# STM32BluePill.net
KiCad netlist of a schematic drawn in EAGLE
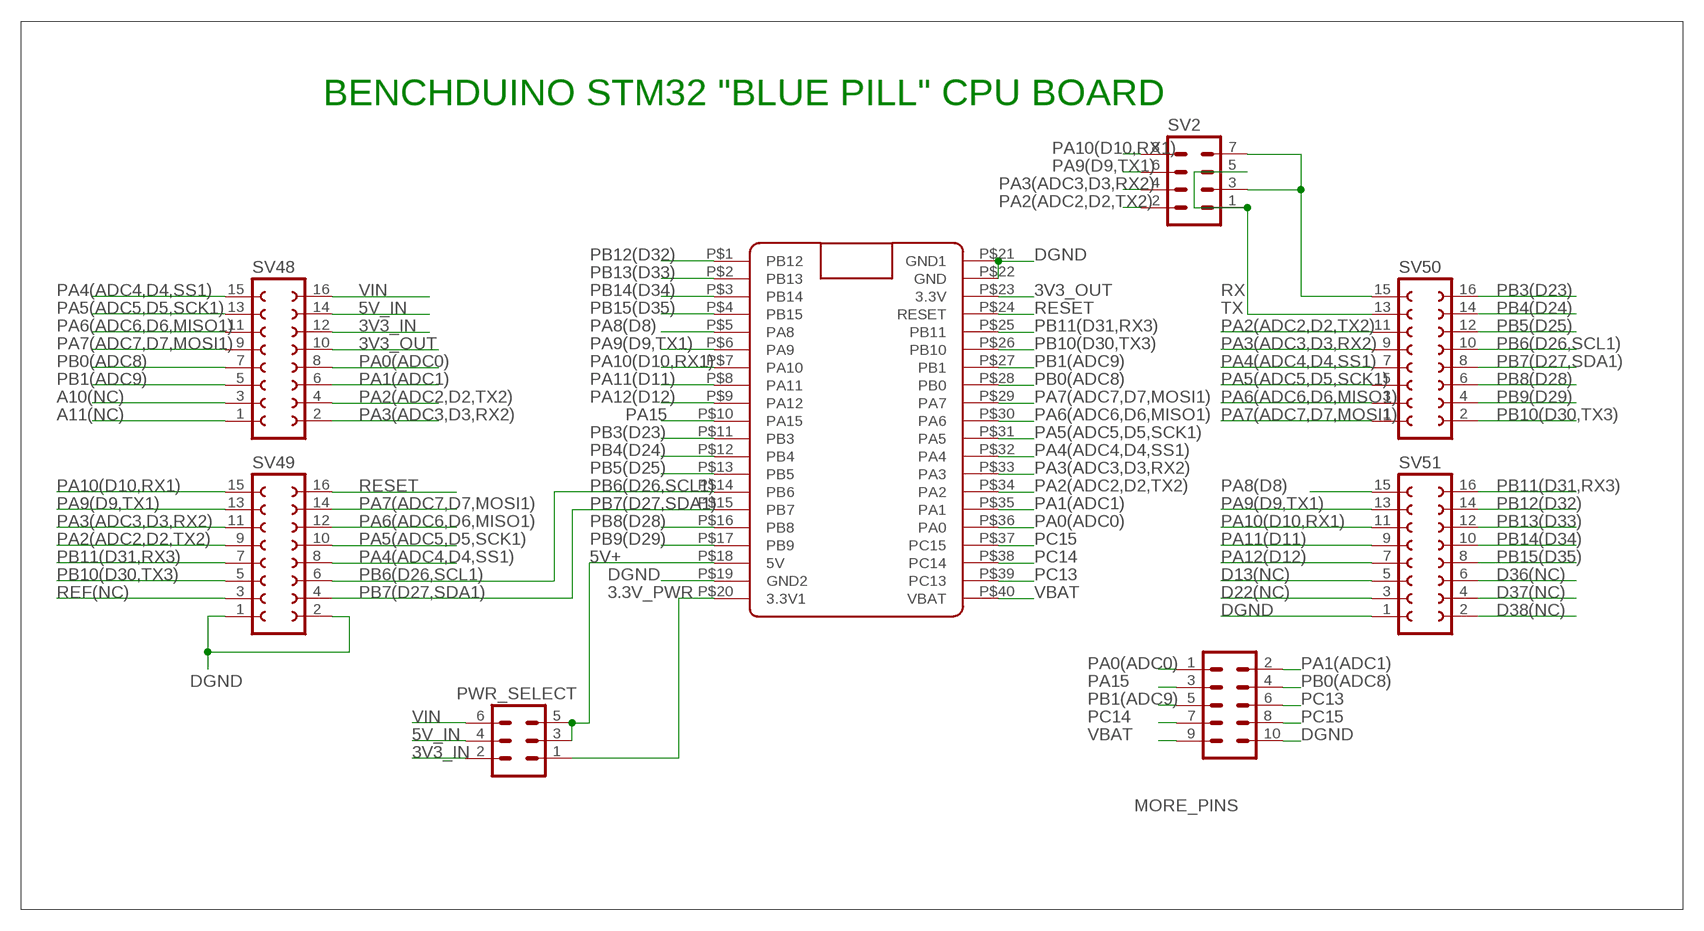
[diagram p0: schematic, sheet 1]

(export (version "E")
  (design (tool "Eeschema 10.0.6"))
  (components
    (comp (ref "MORE_PINS")
      (value "MA05-2")
      (footprint "eagle-import:MA05-2")
      (libsource (lib "eagle-import") (part "MA05-2"))
    )
    (comp (ref "PWR_SELECT")
      (value "MA03-2")
      (footprint "eagle-import:MA03-2")
      (libsource (lib "eagle-import") (part "MA03-2"))
    )
    (comp (ref "SV2")
      (value "MA04-2")
      (footprint "eagle-import:MA04-2")
      (libsource (lib "eagle-import") (part "MA04-2"))
    )
    (comp (ref "SV48")
      (value "FE08-2")
      (footprint "eagle-import:FE08-2")
      (libsource (lib "eagle-import") (part "FE08-2"))
    )
    (comp (ref "SV49")
      (value "FE08-2")
      (footprint "eagle-import:FE08-2")
      (libsource (lib "eagle-import") (part "FE08-2"))
    )
    (comp (ref "SV50")
      (value "FE08-2")
      (footprint "eagle-import:FE08-2")
      (libsource (lib "eagle-import") (part "FE08-2"))
    )
    (comp (ref "SV51")
      (value "FE08-2")
      (footprint "eagle-import:FE08-2")
      (libsource (lib "eagle-import") (part "FE08-2"))
    )
    (comp (ref "U$1")
      (value "BLUE_PILLADVANCED")
      (footprint "eagle-import:BLUE_PILL_ADV")
      (libsource (lib "eagle-import") (part "BLUE_PILLADVANCED"))
    )
  )
  (nets
    (net (code "1") (name "3.3V_PWR") (class "Default")
      (node (ref "PWR_SELECT") (pin "1") (pinfunction "1_1") (pintype "passive"))
      (node (ref "U$1") (pin "P$20") (pinfunction "3.3V1_P$20") (pintype "bidirectional"))
    )
    (net (code "2") (name "3V3_IN") (class "Default")
      (node (ref "PWR_SELECT") (pin "2") (pinfunction "2_2") (pintype "passive"))
      (node (ref "SV48") (pin "12") (pinfunction "12_12") (pintype "passive"))
    )
    (net (code "3") (name "3V3_OUT") (class "Default")
      (node (ref "SV48") (pin "10") (pinfunction "10_10") (pintype "passive"))
      (node (ref "U$1") (pin "P$23") (pinfunction "3.3V_P$23") (pintype "bidirectional"))
    )
    (net (code "4") (name "5V+") (class "Default")
      (node (ref "PWR_SELECT") (pin "3") (pinfunction "3_3") (pintype "passive"))
      (node (ref "PWR_SELECT") (pin "5") (pinfunction "5_5") (pintype "passive"))
      (node (ref "U$1") (pin "P$18") (pinfunction "5V_P$18") (pintype "bidirectional"))
    )
    (net (code "5") (name "5V_IN") (class "Default")
      (node (ref "PWR_SELECT") (pin "4") (pinfunction "4_4") (pintype "passive"))
      (node (ref "SV48") (pin "14") (pinfunction "14_14") (pintype "passive"))
    )
    (net (code "6") (name "A10(NC)") (class "Default")
      (node (ref "SV48") (pin "3") (pinfunction "3_3") (pintype "passive"))
    )
    (net (code "7") (name "A11(NC)") (class "Default")
      (node (ref "SV48") (pin "1") (pinfunction "1_1") (pintype "passive"))
    )
    (net (code "8") (name "D13(NC)") (class "Default")
      (node (ref "SV51") (pin "5") (pinfunction "5_5") (pintype "passive"))
    )
    (net (code "9") (name "D22(NC)") (class "Default")
      (node (ref "SV51") (pin "3") (pinfunction "3_3") (pintype "passive"))
    )
    (net (code "10") (name "D36(NC)") (class "Default")
      (node (ref "SV51") (pin "6") (pinfunction "6_6") (pintype "passive"))
    )
    (net (code "11") (name "D37(NC)") (class "Default")
      (node (ref "SV51") (pin "4") (pinfunction "4_4") (pintype "passive"))
    )
    (net (code "12") (name "D38(NC)") (class "Default")
      (node (ref "SV51") (pin "2") (pinfunction "2_2") (pintype "passive"))
    )
    (net (code "13") (name "DGND") (class "Default")
      (node (ref "MORE_PINS") (pin "10") (pinfunction "10_10") (pintype "passive"))
      (node (ref "SV49") (pin "1") (pinfunction "1_1") (pintype "passive"))
      (node (ref "SV49") (pin "2") (pinfunction "2_2") (pintype "passive"))
      (node (ref "SV51") (pin "1") (pinfunction "1_1") (pintype "passive"))
      (node (ref "U$1") (pin "P$19") (pinfunction "GND2_P$19") (pintype "bidirectional"))
      (node (ref "U$1") (pin "P$21") (pinfunction "GND1_P$21") (pintype "power_in"))
      (node (ref "U$1") (pin "P$22") (pinfunction "GND_P$22") (pintype "bidirectional"))
    )
    (net (code "14") (name "PA0(ADC0)") (class "Default")
      (node (ref "MORE_PINS") (pin "1") (pinfunction "1_1") (pintype "passive"))
      (node (ref "SV48") (pin "8") (pinfunction "8_8") (pintype "passive"))
      (node (ref "U$1") (pin "P$36") (pinfunction "PA0_P$36") (pintype "bidirectional"))
    )
    (net (code "15") (name "PA1(ADC1)") (class "Default")
      (node (ref "MORE_PINS") (pin "2") (pinfunction "2_2") (pintype "passive"))
      (node (ref "SV48") (pin "6") (pinfunction "6_6") (pintype "passive"))
      (node (ref "U$1") (pin "P$35") (pinfunction "PA1_P$35") (pintype "bidirectional"))
    )
    (net (code "16") (name "PA2(ADC2,D2,TX2)") (class "Default")
      (node (ref "SV2") (pin "2") (pinfunction "2_2") (pintype "passive"))
      (node (ref "SV48") (pin "4") (pinfunction "4_4") (pintype "passive"))
      (node (ref "SV49") (pin "9") (pinfunction "9_9") (pintype "passive"))
      (node (ref "SV50") (pin "11") (pinfunction "11_11") (pintype "passive"))
      (node (ref "U$1") (pin "P$34") (pinfunction "PA2_P$34") (pintype "bidirectional"))
    )
    (net (code "17") (name "PA3(ADC3,D3,RX2)") (class "Default")
      (node (ref "SV2") (pin "4") (pinfunction "4_4") (pintype "passive"))
      (node (ref "SV48") (pin "2") (pinfunction "2_2") (pintype "passive"))
      (node (ref "SV49") (pin "11") (pinfunction "11_11") (pintype "passive"))
      (node (ref "SV50") (pin "9") (pinfunction "9_9") (pintype "passive"))
      (node (ref "U$1") (pin "P$33") (pinfunction "PA3_P$33") (pintype "bidirectional"))
    )
    (net (code "18") (name "PA4(ADC4,D4,SS1)") (class "Default")
      (node (ref "SV48") (pin "15") (pinfunction "15_15") (pintype "passive"))
      (node (ref "SV49") (pin "8") (pinfunction "8_8") (pintype "passive"))
      (node (ref "SV50") (pin "7") (pinfunction "7_7") (pintype "passive"))
      (node (ref "U$1") (pin "P$32") (pinfunction "PA4_P$32") (pintype "bidirectional"))
    )
    (net (code "19") (name "PA5(ADC5,D5,SCK1)") (class "Default")
      (node (ref "SV48") (pin "13") (pinfunction "13_13") (pintype "passive"))
      (node (ref "SV49") (pin "10") (pinfunction "10_10") (pintype "passive"))
      (node (ref "SV50") (pin "5") (pinfunction "5_5") (pintype "passive"))
      (node (ref "U$1") (pin "P$31") (pinfunction "PA5_P$31") (pintype "bidirectional"))
    )
    (net (code "20") (name "PA6(ADC6,D6,MISO1)") (class "Default")
      (node (ref "SV48") (pin "11") (pinfunction "11_11") (pintype "passive"))
      (node (ref "SV49") (pin "12") (pinfunction "12_12") (pintype "passive"))
      (node (ref "SV50") (pin "3") (pinfunction "3_3") (pintype "passive"))
      (node (ref "U$1") (pin "P$30") (pinfunction "PA6_P$30") (pintype "bidirectional"))
    )
    (net (code "21") (name "PA7(ADC7,D7,MOSI1)") (class "Default")
      (node (ref "SV48") (pin "9") (pinfunction "9_9") (pintype "passive"))
      (node (ref "SV49") (pin "14") (pinfunction "14_14") (pintype "passive"))
      (node (ref "SV50") (pin "1") (pinfunction "1_1") (pintype "passive"))
      (node (ref "U$1") (pin "P$29") (pinfunction "PA7_P$29") (pintype "bidirectional"))
    )
    (net (code "22") (name "PA8(D8)") (class "Default")
      (node (ref "SV51") (pin "15") (pinfunction "15_15") (pintype "passive"))
      (node (ref "U$1") (pin "P$5") (pinfunction "PA8_P$5") (pintype "bidirectional"))
    )
    (net (code "23") (name "PA9(D9,TX1)") (class "Default")
      (node (ref "SV2") (pin "6") (pinfunction "6_6") (pintype "passive"))
      (node (ref "SV49") (pin "13") (pinfunction "13_13") (pintype "passive"))
      (node (ref "SV51") (pin "13") (pinfunction "13_13") (pintype "passive"))
      (node (ref "U$1") (pin "P$6") (pinfunction "PA9_P$6") (pintype "bidirectional"))
    )
    (net (code "24") (name "PA10(D10,RX1)") (class "Default")
      (node (ref "SV2") (pin "8") (pinfunction "8_8") (pintype "passive"))
      (node (ref "SV49") (pin "15") (pinfunction "15_15") (pintype "passive"))
      (node (ref "SV51") (pin "11") (pinfunction "11_11") (pintype "passive"))
      (node (ref "U$1") (pin "P$7") (pinfunction "PA10_P$7") (pintype "bidirectional"))
    )
    (net (code "25") (name "PA11(D11)") (class "Default")
      (node (ref "SV51") (pin "9") (pinfunction "9_9") (pintype "passive"))
      (node (ref "U$1") (pin "P$8") (pinfunction "PA11_P$8") (pintype "bidirectional"))
    )
    (net (code "26") (name "PA12(D12)") (class "Default")
      (node (ref "SV51") (pin "7") (pinfunction "7_7") (pintype "passive"))
      (node (ref "U$1") (pin "P$9") (pinfunction "PA12_P$9") (pintype "bidirectional"))
    )
    (net (code "27") (name "PA15") (class "Default")
      (node (ref "MORE_PINS") (pin "3") (pinfunction "3_3") (pintype "passive"))
      (node (ref "U$1") (pin "P$10") (pinfunction "PA15_P$10") (pintype "bidirectional"))
    )
    (net (code "28") (name "PB0(ADC8)") (class "Default")
      (node (ref "MORE_PINS") (pin "4") (pinfunction "4_4") (pintype "passive"))
      (node (ref "SV48") (pin "7") (pinfunction "7_7") (pintype "passive"))
      (node (ref "U$1") (pin "P$28") (pinfunction "PB0_P$28") (pintype "bidirectional"))
    )
    (net (code "29") (name "PB1(ADC9)") (class "Default")
      (node (ref "MORE_PINS") (pin "5") (pinfunction "5_5") (pintype "passive"))
      (node (ref "SV48") (pin "5") (pinfunction "5_5") (pintype "passive"))
      (node (ref "U$1") (pin "P$27") (pinfunction "PB1_P$27") (pintype "bidirectional"))
    )
    (net (code "30") (name "PB3(D23)") (class "Default")
      (node (ref "SV50") (pin "16") (pinfunction "16_16") (pintype "passive"))
      (node (ref "U$1") (pin "P$11") (pinfunction "PB3_P$11") (pintype "bidirectional"))
    )
    (net (code "31") (name "PB4(D24)") (class "Default")
      (node (ref "SV50") (pin "14") (pinfunction "14_14") (pintype "passive"))
      (node (ref "U$1") (pin "P$12") (pinfunction "PB4_P$12") (pintype "bidirectional"))
    )
    (net (code "32") (name "PB5(D25)") (class "Default")
      (node (ref "SV50") (pin "12") (pinfunction "12_12") (pintype "passive"))
      (node (ref "U$1") (pin "P$13") (pinfunction "PB5_P$13") (pintype "bidirectional"))
    )
    (net (code "33") (name "PB6(D26,SCL1)") (class "Default")
      (node (ref "SV49") (pin "6") (pinfunction "6_6") (pintype "passive"))
      (node (ref "SV50") (pin "10") (pinfunction "10_10") (pintype "passive"))
      (node (ref "U$1") (pin "P$14") (pinfunction "PB6_P$14") (pintype "bidirectional"))
    )
    (net (code "34") (name "PB7(D27,SDA1)") (class "Default")
      (node (ref "SV49") (pin "4") (pinfunction "4_4") (pintype "passive"))
      (node (ref "SV50") (pin "8") (pinfunction "8_8") (pintype "passive"))
      (node (ref "U$1") (pin "P$15") (pinfunction "PB7_P$15") (pintype "bidirectional"))
    )
    (net (code "35") (name "PB8(D28)") (class "Default")
      (node (ref "SV50") (pin "6") (pinfunction "6_6") (pintype "passive"))
      (node (ref "U$1") (pin "P$16") (pinfunction "PB8_P$16") (pintype "bidirectional"))
    )
    (net (code "36") (name "PB9(D29)") (class "Default")
      (node (ref "SV50") (pin "4") (pinfunction "4_4") (pintype "passive"))
      (node (ref "U$1") (pin "P$17") (pinfunction "PB9_P$17") (pintype "bidirectional"))
    )
    (net (code "37") (name "PB10(D30,TX3)") (class "Default")
      (node (ref "SV49") (pin "5") (pinfunction "5_5") (pintype "passive"))
      (node (ref "SV50") (pin "2") (pinfunction "2_2") (pintype "passive"))
      (node (ref "U$1") (pin "P$26") (pinfunction "PB10_P$26") (pintype "bidirectional"))
    )
    (net (code "38") (name "PB11(D31,RX3)") (class "Default")
      (node (ref "SV49") (pin "7") (pinfunction "7_7") (pintype "passive"))
      (node (ref "SV51") (pin "16") (pinfunction "16_16") (pintype "passive"))
      (node (ref "U$1") (pin "P$25") (pinfunction "PB11_P$25") (pintype "bidirectional"))
    )
    (net (code "39") (name "PB12(D32)") (class "Default")
      (node (ref "SV51") (pin "14") (pinfunction "14_14") (pintype "passive"))
      (node (ref "U$1") (pin "P$1") (pinfunction "PB12_P$1") (pintype "bidirectional"))
    )
    (net (code "40") (name "PB13(D33)") (class "Default")
      (node (ref "SV51") (pin "12") (pinfunction "12_12") (pintype "passive"))
      (node (ref "U$1") (pin "P$2") (pinfunction "PB13_P$2") (pintype "bidirectional"))
    )
    (net (code "41") (name "PB14(D34)") (class "Default")
      (node (ref "SV51") (pin "10") (pinfunction "10_10") (pintype "passive"))
      (node (ref "U$1") (pin "P$3") (pinfunction "PB14_P$3") (pintype "bidirectional"))
    )
    (net (code "42") (name "PB15(D35)") (class "Default")
      (node (ref "SV51") (pin "8") (pinfunction "8_8") (pintype "passive"))
      (node (ref "U$1") (pin "P$4") (pinfunction "PB15_P$4") (pintype "bidirectional"))
    )
    (net (code "43") (name "PC13") (class "Default")
      (node (ref "MORE_PINS") (pin "6") (pinfunction "6_6") (pintype "passive"))
      (node (ref "U$1") (pin "P$39") (pinfunction "PC13_P$39") (pintype "bidirectional"))
    )
    (net (code "44") (name "PC14") (class "Default")
      (node (ref "MORE_PINS") (pin "7") (pinfunction "7_7") (pintype "passive"))
      (node (ref "U$1") (pin "P$38") (pinfunction "PC14_P$38") (pintype "bidirectional"))
    )
    (net (code "45") (name "PC15") (class "Default")
      (node (ref "MORE_PINS") (pin "8") (pinfunction "8_8") (pintype "passive"))
      (node (ref "U$1") (pin "P$37") (pinfunction "PC15_P$37") (pintype "bidirectional"))
    )
    (net (code "46") (name "REF(NC)") (class "Default")
      (node (ref "SV49") (pin "3") (pinfunction "3_3") (pintype "passive"))
    )
    (net (code "47") (name "RESET") (class "Default")
      (node (ref "SV49") (pin "16") (pinfunction "16_16") (pintype "passive"))
      (node (ref "U$1") (pin "P$24") (pinfunction "RESET_P$24") (pintype "bidirectional"))
    )
    (net (code "48") (name "RX") (class "Default")
      (node (ref "SV2") (pin "3") (pinfunction "3_3") (pintype "passive"))
      (node (ref "SV2") (pin "7") (pinfunction "7_7") (pintype "passive"))
      (node (ref "SV50") (pin "15") (pinfunction "15_15") (pintype "passive"))
    )
    (net (code "49") (name "TX") (class "Default")
      (node (ref "SV2") (pin "1") (pinfunction "1_1") (pintype "passive"))
      (node (ref "SV2") (pin "5") (pinfunction "5_5") (pintype "passive"))
      (node (ref "SV50") (pin "13") (pinfunction "13_13") (pintype "passive"))
    )
    (net (code "50") (name "VBAT") (class "Default")
      (node (ref "MORE_PINS") (pin "9") (pinfunction "9_9") (pintype "passive"))
      (node (ref "U$1") (pin "P$40") (pinfunction "VBAT_P$40") (pintype "bidirectional"))
    )
    (net (code "51") (name "VIN") (class "Default")
      (node (ref "PWR_SELECT") (pin "6") (pinfunction "6_6") (pintype "passive"))
      (node (ref "SV48") (pin "16") (pinfunction "16_16") (pintype "passive"))
    )
  )
)
